# Hochbeet_2020-04-23_13-35-51.net
KiCad netlist of a schematic drawn in EasyEDA
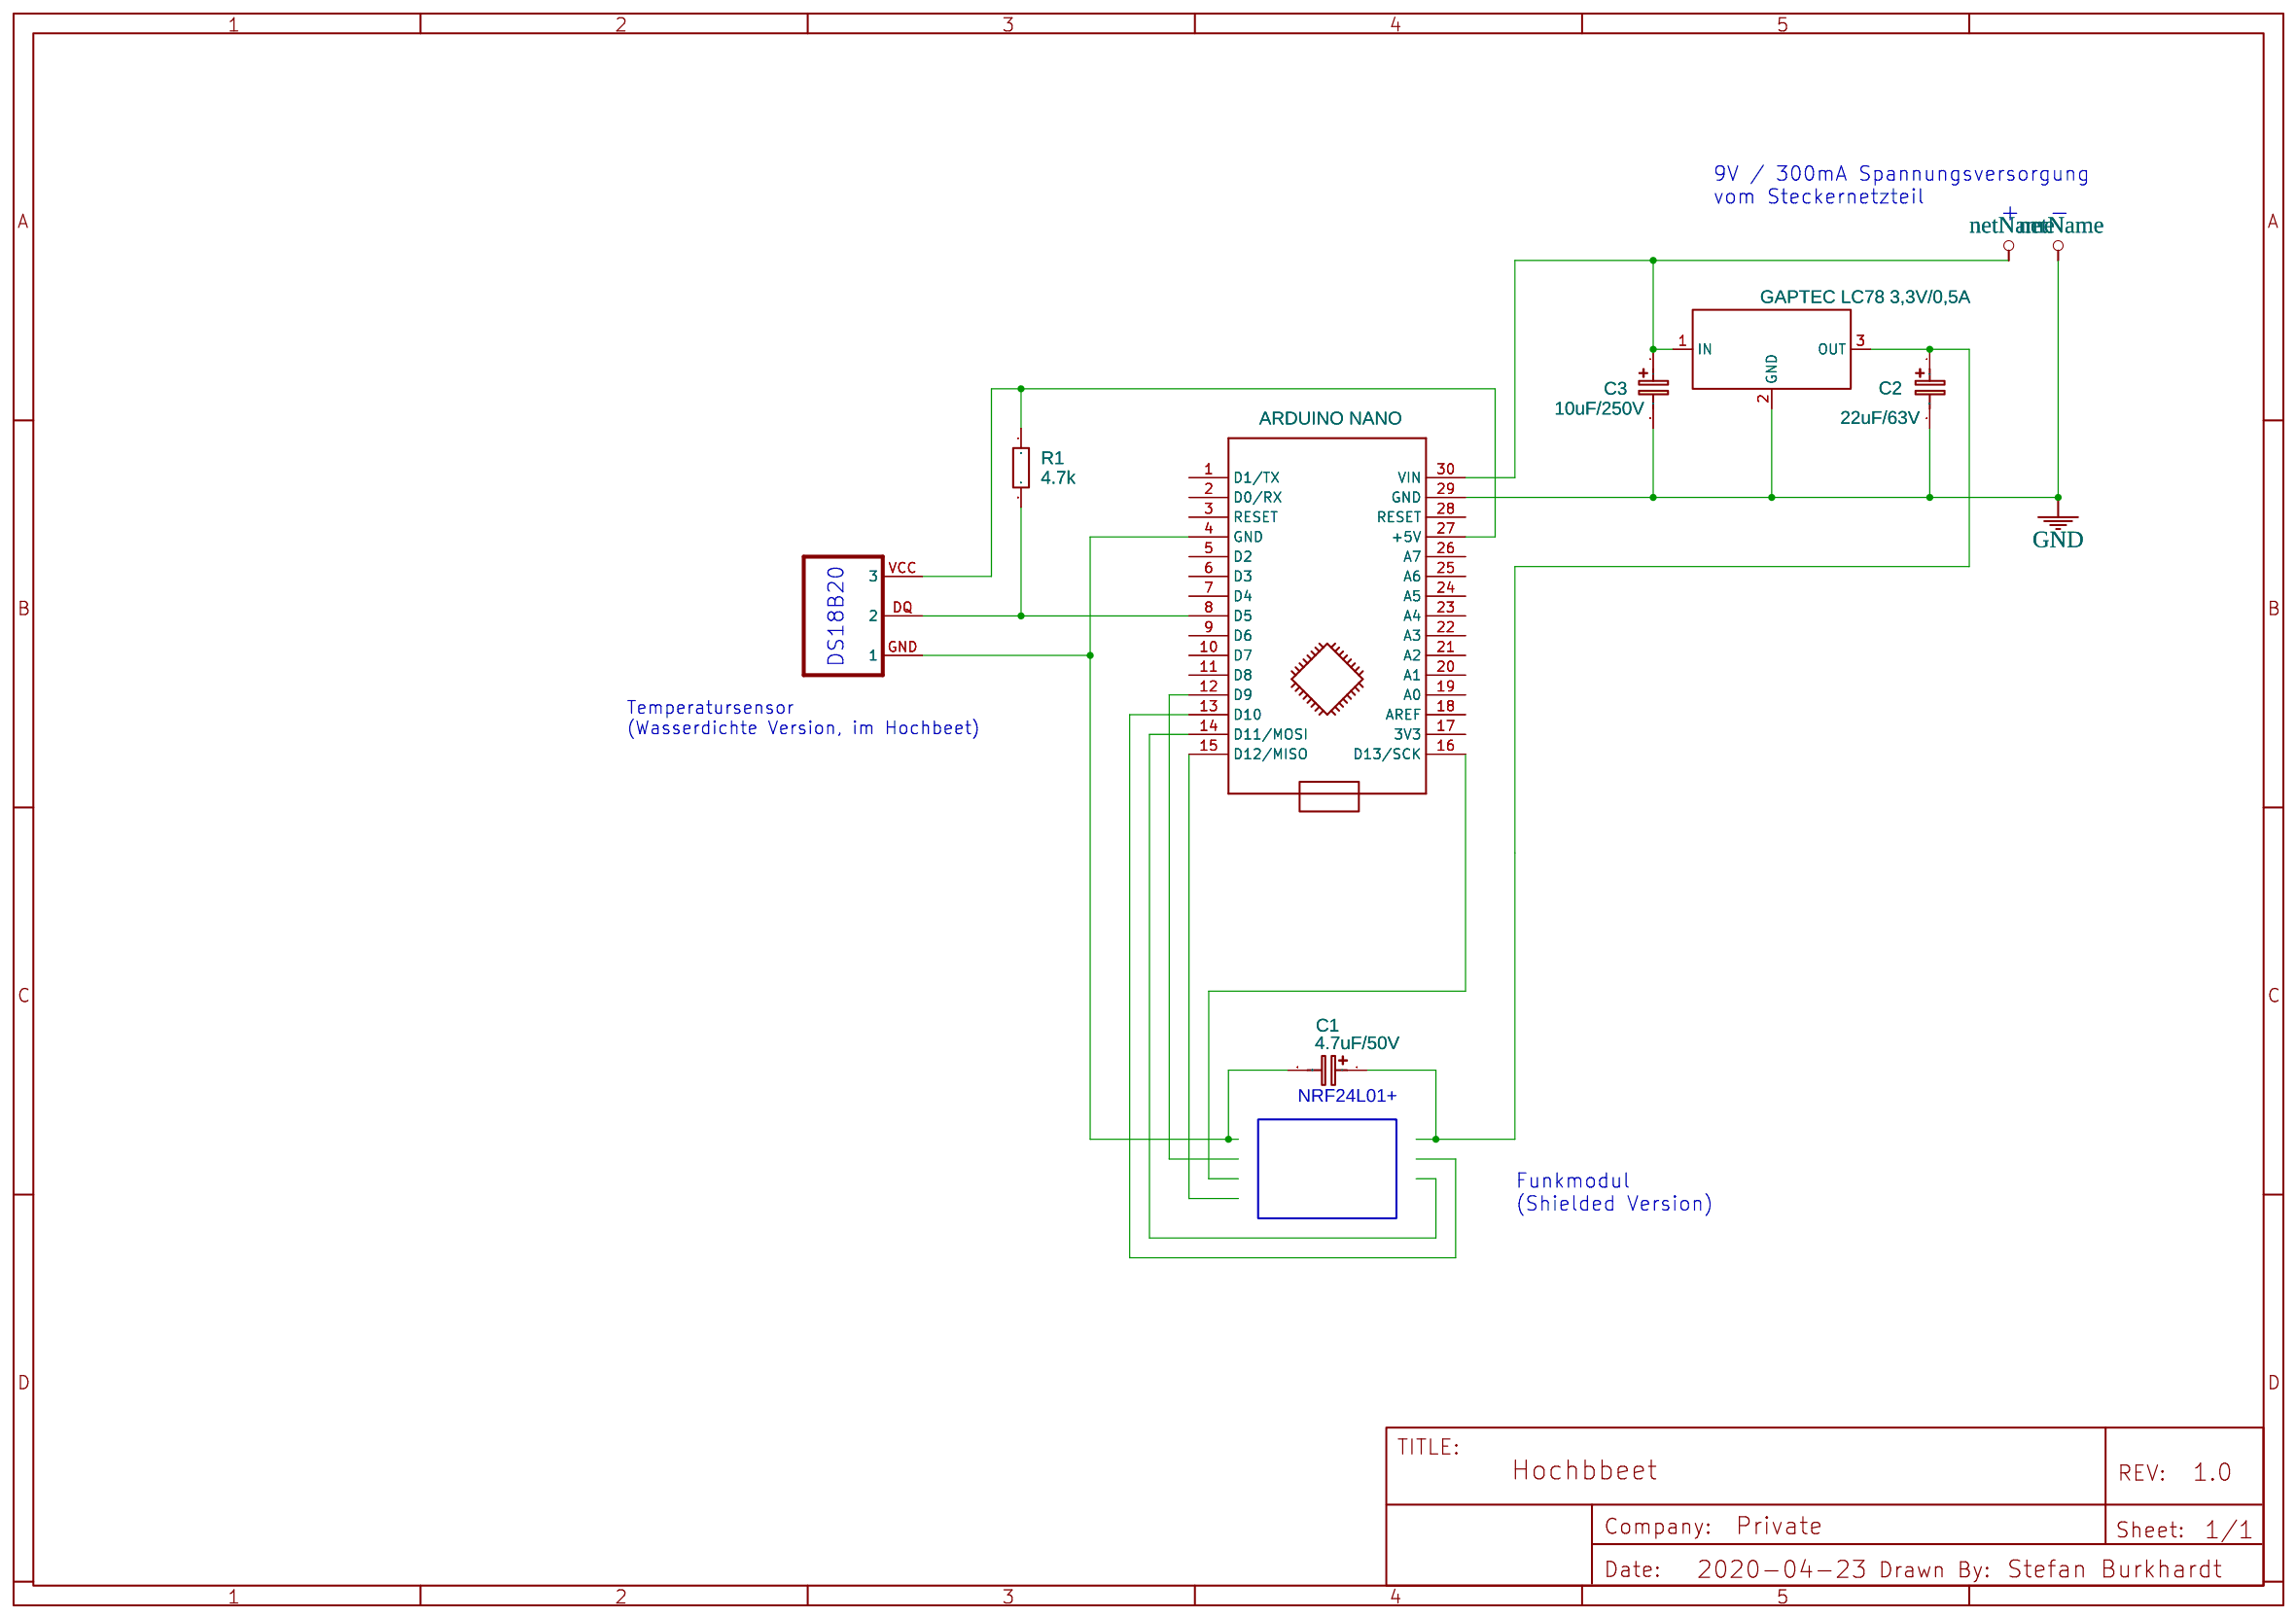
[diagram p0: schematic sheet]

(export (version "E")
  (design (tool "Eeschema 10.0.6"))
  (components
    (comp (ref "C1")
      (value "4.7uF/50V")
      (fields (field (name "BOM_Manufacturer Part") "?"))
      (libsource (lib "") (part "Cap_Electrolytic(TH)_D3.0XF1.5_EU_1"))
    )
    (comp (ref "C2")
      (value "22uF/63V")
      (fields (field (name "BOM_Manufacturer Part") "?"))
      (libsource (lib "") (part "Cap_Electrolytic(TH)_D3.0XF1.5_EU"))
    )
    (comp (ref "C3")
      (value "10uF/250V")
      (fields (field (name "BOM_Manufacturer Part") "?"))
      (libsource (lib "") (part "Cap_Electrolytic(TH)_D3.0XF1.5_EU"))
    )
    (comp (ref "R1")
      (value "4.7k")
      (fields (field (name "BOM_Manufacturer Part") "?"))
      (libsource (lib "") (part "Res_AXIAL-0.3(1/8W)_EU"))
    )
    (comp (ref "U1")
      (value "ARDUINO NANO")
      (fields (field (name "BOM_Manufacturer Part") "?"))
      (libsource (lib "") (part "Unknown_665_310"))
    )
    (comp (ref "U2")
      (value "DS18B20")
      (fields (field (name "BOM_Manufacturer Part") "?"))
      (libsource (lib "") (part "Unknown_460_325"))
    )
    (comp (ref "U4")
      (value "GAPTEC LC78 3,3V/0,5A")
      (fields (field (name "BOM_Manufacturer Part") "?"))
      (libsource (lib "") (part "Unknown_890_170"))
    )
  )
  (nets
    (net (code "1") (name "GND") (class "Default")
      (node (ref "C2") (pin "2") (pinfunction "2_2") (pintype "unspecified"))
      (node (ref "C3") (pin "1") (pinfunction "1_1") (pintype "unspecified"))
      (node (ref "C3") (pin "2") (pinfunction "2_2") (pintype "unspecified"))
      (node (ref "U1") (pin "29") (pinfunction "GND_29") (pintype "unspecified"))
      (node (ref "U1") (pin "30") (pinfunction "VIN_30") (pintype "unspecified"))
      (node (ref "U4") (pin "1") (pinfunction "IN_1") (pintype "unspecified"))
      (node (ref "U4") (pin "2") (pinfunction "GND_2") (pintype "unspecified"))
    )
    (net (code "2") (name "Net-(U1-+5V)") (class "Default")
      (node (ref "R1") (pin "1") (pinfunction "1_1") (pintype "unspecified"))
      (node (ref "U1") (pin "27") (pinfunction "+5V_27") (pintype "unspecified"))
      (node (ref "U2") (pin "VCC") (pinfunction "3_VCC") (pintype "unspecified"))
    )
    (net (code "3") (name "Net-(U1-D5)") (class "Default")
      (node (ref "R1") (pin "2") (pinfunction "2_2") (pintype "unspecified"))
      (node (ref "U1") (pin "8") (pinfunction "D5_8") (pintype "unspecified"))
      (node (ref "U2") (pin "DQ") (pinfunction "2_DQ") (pintype "unspecified"))
    )
    (net (code "4") (name "Net-(U2-1)") (class "Default")
      (node (ref "C1") (pin "2") (pinfunction "2_2") (pintype "unspecified"))
      (node (ref "U1") (pin "4") (pinfunction "GND_4") (pintype "unspecified"))
      (node (ref "U2") (pin "GND") (pinfunction "1_GND") (pintype "unspecified"))
    )
    (net (code "5") (name "Net-(U4-OUT)") (class "Default")
      (node (ref "C1") (pin "1") (pinfunction "1_1") (pintype "unspecified"))
      (node (ref "C2") (pin "1") (pinfunction "1_1") (pintype "unspecified"))
      (node (ref "U4") (pin "3") (pinfunction "OUT_3") (pintype "unspecified"))
    )
    (net (code "6") (name "unconnected-(U1-3V3-Pad17)") (class "Default")
      (node (ref "U1") (pin "17") (pinfunction "3V3_17") (pintype "unspecified"))
    )
    (net (code "7") (name "unconnected-(U1-A0-Pad19)") (class "Default")
      (node (ref "U1") (pin "19") (pinfunction "A0_19") (pintype "unspecified"))
    )
    (net (code "8") (name "unconnected-(U1-A1-Pad20)") (class "Default")
      (node (ref "U1") (pin "20") (pinfunction "A1_20") (pintype "unspecified"))
    )
    (net (code "9") (name "unconnected-(U1-A2-Pad21)") (class "Default")
      (node (ref "U1") (pin "21") (pinfunction "A2_21") (pintype "unspecified"))
    )
    (net (code "10") (name "unconnected-(U1-A3-Pad22)") (class "Default")
      (node (ref "U1") (pin "22") (pinfunction "A3_22") (pintype "unspecified"))
    )
    (net (code "11") (name "unconnected-(U1-A4-Pad23)") (class "Default")
      (node (ref "U1") (pin "23") (pinfunction "A4_23") (pintype "unspecified"))
    )
    (net (code "12") (name "unconnected-(U1-A5-Pad24)") (class "Default")
      (node (ref "U1") (pin "24") (pinfunction "A5_24") (pintype "unspecified"))
    )
    (net (code "13") (name "unconnected-(U1-A6-Pad25)") (class "Default")
      (node (ref "U1") (pin "25") (pinfunction "A6_25") (pintype "unspecified"))
    )
    (net (code "14") (name "unconnected-(U1-A7-Pad26)") (class "Default")
      (node (ref "U1") (pin "26") (pinfunction "A7_26") (pintype "unspecified"))
    )
    (net (code "15") (name "unconnected-(U1-AREF-Pad18)") (class "Default")
      (node (ref "U1") (pin "18") (pinfunction "AREF_18") (pintype "unspecified"))
    )
    (net (code "16") (name "unconnected-(U1-D0{slash}RX-Pad2)") (class "Default")
      (node (ref "U1") (pin "2") (pinfunction "D0/RX_2") (pintype "unspecified"))
    )
    (net (code "17") (name "unconnected-(U1-D1{slash}TX-Pad1)") (class "Default")
      (node (ref "U1") (pin "1") (pinfunction "D1/TX_1") (pintype "unspecified"))
    )
    (net (code "18") (name "unconnected-(U1-D2-Pad5)") (class "Default")
      (node (ref "U1") (pin "5") (pinfunction "D2_5") (pintype "unspecified"))
    )
    (net (code "19") (name "unconnected-(U1-D3-Pad6)") (class "Default")
      (node (ref "U1") (pin "6") (pinfunction "D3_6") (pintype "unspecified"))
    )
    (net (code "20") (name "unconnected-(U1-D4-Pad7)") (class "Default")
      (node (ref "U1") (pin "7") (pinfunction "D4_7") (pintype "unspecified"))
    )
    (net (code "21") (name "unconnected-(U1-D6-Pad9)") (class "Default")
      (node (ref "U1") (pin "9") (pinfunction "D6_9") (pintype "unspecified"))
    )
    (net (code "22") (name "unconnected-(U1-D7-Pad10)") (class "Default")
      (node (ref "U1") (pin "10") (pinfunction "D7_10") (pintype "unspecified"))
    )
    (net (code "23") (name "unconnected-(U1-D8-Pad11)") (class "Default")
      (node (ref "U1") (pin "11") (pinfunction "D8_11") (pintype "unspecified"))
    )
    (net (code "24") (name "unconnected-(U1-D9-Pad12)") (class "Default")
      (node (ref "U1") (pin "12") (pinfunction "D9_12") (pintype "unspecified"))
    )
    (net (code "25") (name "unconnected-(U1-D10-Pad13)") (class "Default")
      (node (ref "U1") (pin "13") (pinfunction "D10_13") (pintype "unspecified"))
    )
    (net (code "26") (name "unconnected-(U1-D11{slash}MOSI-Pad14)") (class "Default")
      (node (ref "U1") (pin "14") (pinfunction "D11/MOSI_14") (pintype "unspecified"))
    )
    (net (code "27") (name "unconnected-(U1-D12{slash}MISO-Pad15)") (class "Default")
      (node (ref "U1") (pin "15") (pinfunction "D12/MISO_15") (pintype "unspecified"))
    )
    (net (code "28") (name "unconnected-(U1-D13{slash}SCK-Pad16)") (class "Default")
      (node (ref "U1") (pin "16") (pinfunction "D13/SCK_16") (pintype "unspecified"))
    )
    (net (code "29") (name "unconnected-(U1-RESET-Pad3)") (class "Default")
      (node (ref "U1") (pin "3") (pinfunction "RESET_3") (pintype "unspecified"))
    )
    (net (code "30") (name "unconnected-(U1-RESET-Pad28)") (class "Default")
      (node (ref "U1") (pin "28") (pinfunction "RESET_28") (pintype "unspecified"))
    )
  )
)
